# Sheet3.net
KiCad netlist of a schematic drawn in Altium Designer
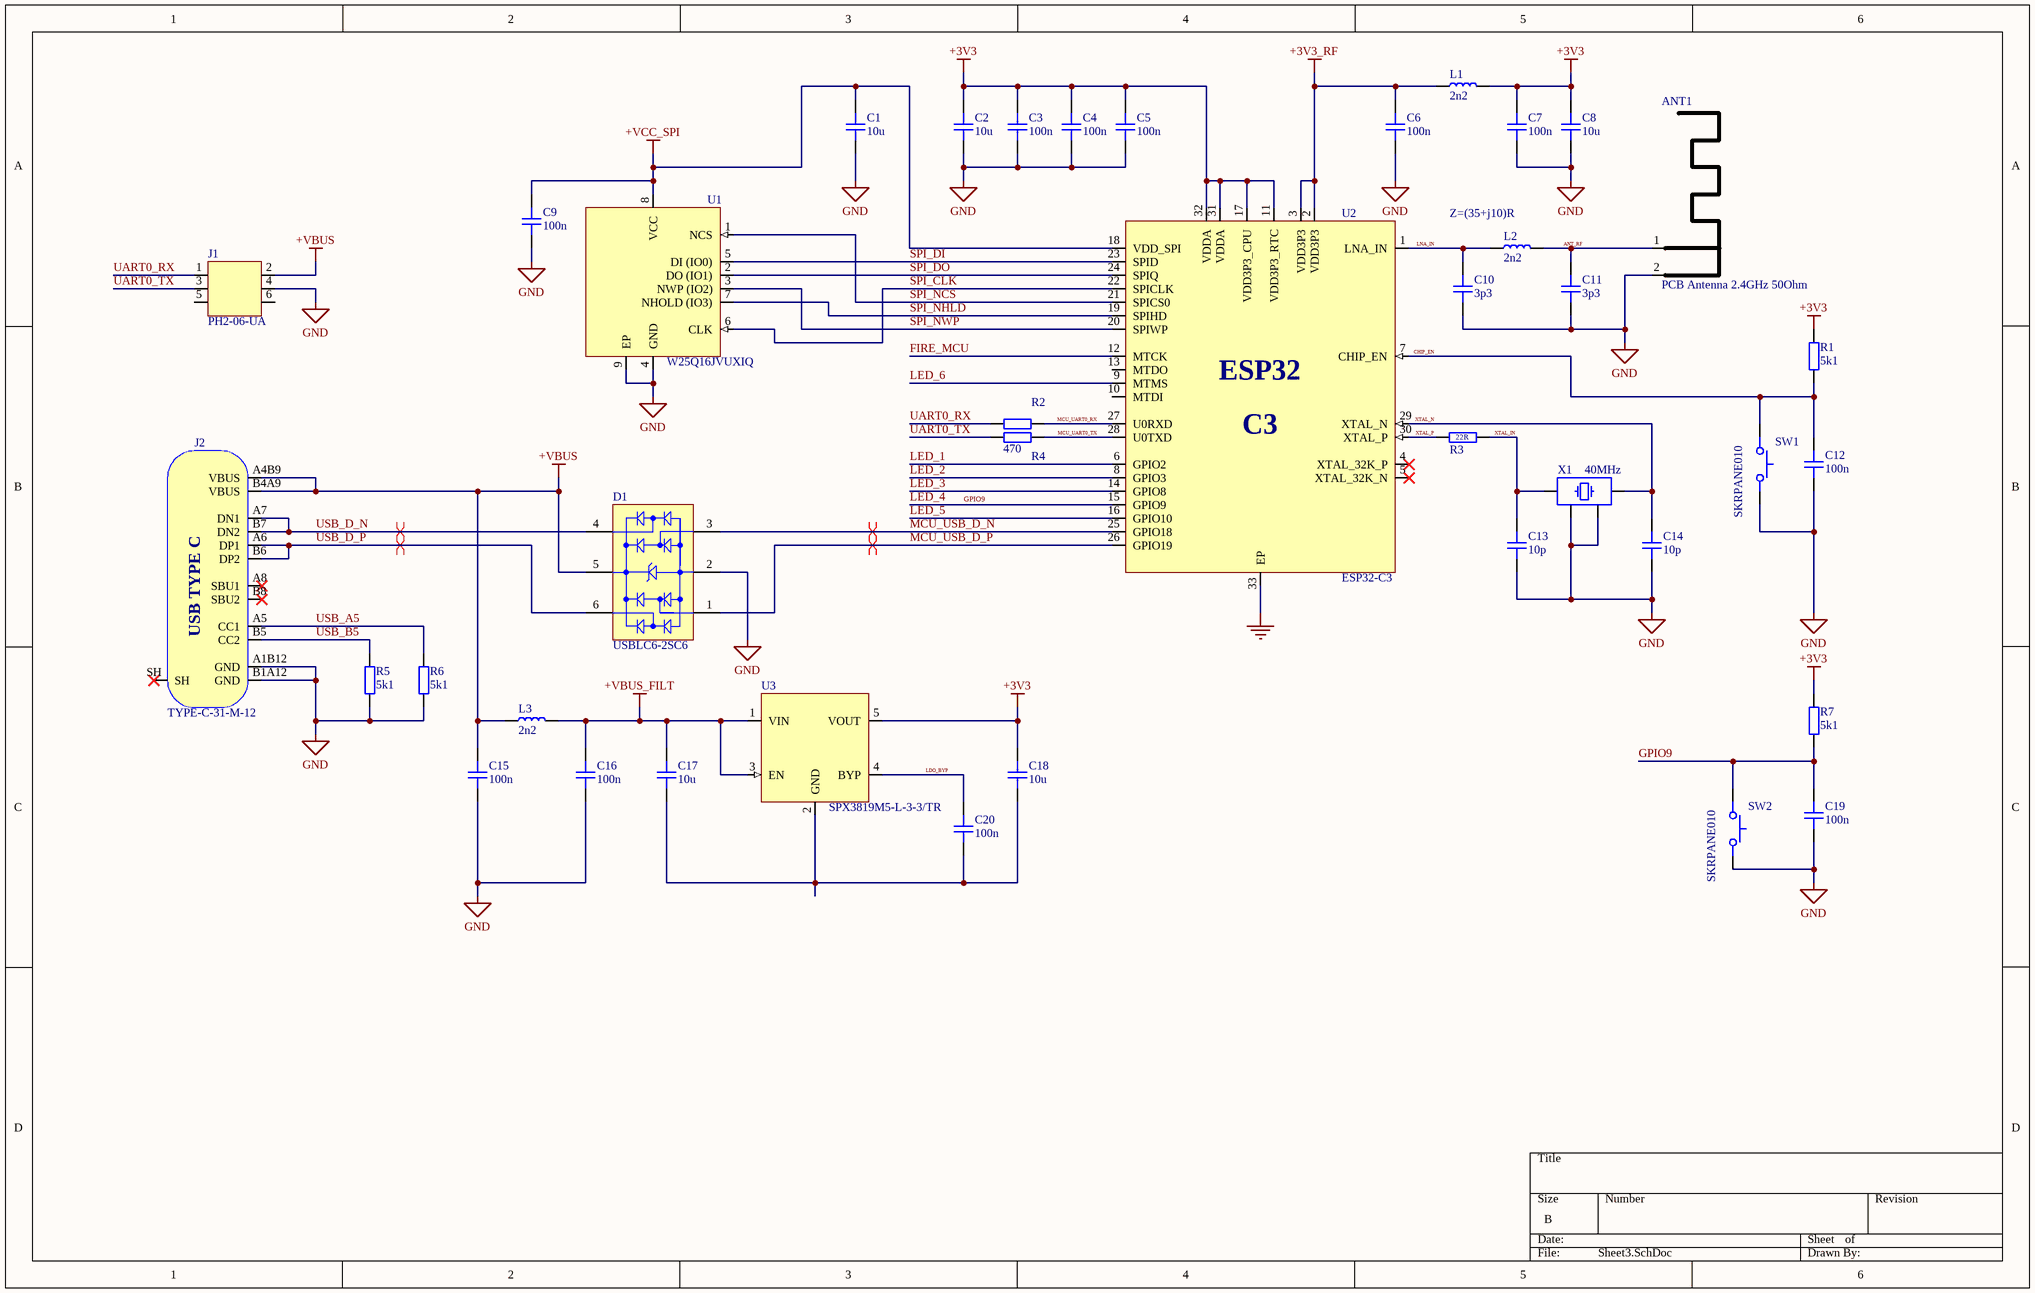
[diagram p0: Sheet3.SchDoc]

(export (version "E")
  (design (tool "Eeschema 10.0.6"))
  (components
    (comp (ref "ANT1")
      (value "PCB Antenna 2.4GHz 50Ohm")
      (footprint "ANT_IFA_USB_2_4GHZ_50R")
      (description "Inverted F 2.4GHz ISM PCB Antenna 50 Ohm")
      (libsource (lib "Schematic-Lib-PhilsLab") (part "ANT_IFA_USB_2_4GHZ_50R"))
    )
    (comp (ref "C1")
      (value "10u")
      (footprint "CAP_0603")
      (description "Capacitor SMD 0603 10V")
      (fields
        (field (name "MANUFACTURER") "Samsung")
        (field (name "MANUFACTURER PART NUMBER") "CL10A106KP8NNNC")
      )
      (libsource (lib "Schematic-Lib-PhilsLab") (part "CAP_0603_10V"))
    )
    (comp (ref "C2")
      (value "10u")
      (footprint "CAP_0603")
      (description "Capacitor SMD 0603 10V")
      (fields
        (field (name "MANUFACTURER") "Samsung")
        (field (name "MANUFACTURER PART NUMBER") "CL10A106KP8NNNC")
      )
      (libsource (lib "Schematic-Lib-PhilsLab") (part "CAP_0603_10V"))
    )
    (comp (ref "C3")
      (value "100n")
      (footprint "CAP_0805")
      (description "Capacitor SMD 0805 50V")
      (libsource (lib "Schematic-Lib-PhilsLab") (part "CAP_0805_50V"))
    )
    (comp (ref "C4")
      (value "100n")
      (footprint "CAP_0805")
      (description "Capacitor SMD 0805 50V")
      (libsource (lib "Schematic-Lib-PhilsLab") (part "CAP_0805_50V"))
    )
    (comp (ref "C5")
      (value "100n")
      (footprint "CAP_0805")
      (description "Capacitor SMD 0805 50V")
      (libsource (lib "Schematic-Lib-PhilsLab") (part "CAP_0805_50V"))
    )
    (comp (ref "C6")
      (value "100n")
      (footprint "CAP_0805")
      (description "Capacitor SMD 0805 50V")
      (libsource (lib "Schematic-Lib-PhilsLab") (part "CAP_0805_50V"))
    )
    (comp (ref "C7")
      (value "100n")
      (footprint "CAP_0805")
      (description "Capacitor SMD 0805 50V")
      (libsource (lib "Schematic-Lib-PhilsLab") (part "CAP_0805_50V"))
    )
    (comp (ref "C8")
      (value "10u")
      (footprint "CAP_0603")
      (description "Capacitor SMD 0603 10V")
      (fields
        (field (name "MANUFACTURER") "Samsung")
        (field (name "MANUFACTURER PART NUMBER") "CL10A106KP8NNNC")
      )
      (libsource (lib "Schematic-Lib-PhilsLab") (part "CAP_0603_10V"))
    )
    (comp (ref "C9")
      (value "100n")
      (footprint "CAP_0805")
      (description "Capacitor SMD 0805 50V")
      (libsource (lib "Schematic-Lib-PhilsLab") (part "CAP_0805_50V"))
    )
    (comp (ref "C10")
      (value "3p3")
      (footprint "CAP_0402")
      (description "Capacitor SMD 0402 50V")
      (fields (field (name "MANUFACTURER") "FH") (field (name "MANUFACTURER PART NUMBER") "0402CG3R3C500NT"))
      (libsource (lib "Schematic-Lib-PhilsLab") (part "CAP_0402_50V"))
    )
    (comp (ref "C11")
      (value "3p3")
      (footprint "CAP_0402")
      (description "Capacitor SMD 0402 50V")
      (fields (field (name "MANUFACTURER") "FH") (field (name "MANUFACTURER PART NUMBER") "0402CG3R3C500NT"))
      (libsource (lib "Schematic-Lib-PhilsLab") (part "CAP_0402_50V"))
    )
    (comp (ref "C12")
      (value "100n")
      (footprint "CAP_0805")
      (description "Capacitor SMD 0805 50V")
      (libsource (lib "Schematic-Lib-PhilsLab") (part "CAP_0805_50V"))
    )
    (comp (ref "C13")
      (value "10p")
      (footprint "CAP_0402")
      (description "Capacitor SMD 0402 50V")
      (fields
        (field (name "MANUFACTURER") "Samsung")
        (field (name "MANUFACTURER PART NUMBER") "CL05C100JB5NNNC")
      )
      (libsource (lib "Schematic-Lib-PhilsLab") (part "CAP_0402_50V"))
    )
    (comp (ref "C14")
      (value "10p")
      (footprint "CAP_0402")
      (description "Capacitor SMD 0402 50V")
      (fields
        (field (name "MANUFACTURER") "Samsung")
        (field (name "MANUFACTURER PART NUMBER") "CL05C100JB5NNNC")
      )
      (libsource (lib "Schematic-Lib-PhilsLab") (part "CAP_0402_50V"))
    )
    (comp (ref "C15")
      (value "100n")
      (footprint "CAP_0805")
      (description "Capacitor SMD 0805 50V")
      (libsource (lib "Schematic-Lib-PhilsLab") (part "CAP_0805_50V"))
    )
    (comp (ref "C16")
      (value "100n")
      (footprint "CAP_0805")
      (description "Capacitor SMD 0805 50V")
      (libsource (lib "Schematic-Lib-PhilsLab") (part "CAP_0805_50V"))
    )
    (comp (ref "C17")
      (value "10u")
      (footprint "CAP_0603")
      (description "Capacitor SMD 0603 10V")
      (fields
        (field (name "MANUFACTURER") "Samsung")
        (field (name "MANUFACTURER PART NUMBER") "CL10A106KP8NNNC")
      )
      (libsource (lib "Schematic-Lib-PhilsLab") (part "CAP_0603_10V"))
    )
    (comp (ref "C18")
      (value "10u")
      (footprint "CAP_0603")
      (description "Capacitor SMD 0603 10V")
      (fields
        (field (name "MANUFACTURER") "Samsung")
        (field (name "MANUFACTURER PART NUMBER") "CL10A106KP8NNNC")
      )
      (libsource (lib "Schematic-Lib-PhilsLab") (part "CAP_0603_10V"))
    )
    (comp (ref "C19")
      (value "100n")
      (footprint "CAP_0805")
      (description "Capacitor SMD 0805 50V")
      (libsource (lib "Schematic-Lib-PhilsLab") (part "CAP_0805_50V"))
    )
    (comp (ref "C20")
      (value "100n")
      (footprint "CAP_0805")
      (description "Capacitor SMD 0805 50V")
      (libsource (lib "Schematic-Lib-PhilsLab") (part "CAP_0805_50V"))
    )
    (comp (ref "D1")
      (value "USBLC6-2SC6")
      (footprint "STM-SOT23-6L_V")
      (description "Very low capacitance ESD protection, 3.5 pF, -40 to 125 degC, 6-Pin SOT23, RoHS, Tape and Reel")
      (fields (field (name "MANUFACTURER") "STMicroelectronics"))
      (libsource (lib "Altium Content Vault") (part "STM-USB_DVI_HDMIULC6-4SC6X-SOT23-6L"))
    )
    (comp (ref "J1")
      (value "PH2-06-UA")
      (footprint "PH2-06-UA")
      (libsource (lib "SchLibrary") (part "PH2-06-UA"))
    )
    (comp (ref "J2")
      (value "TYPE-C-31-M-12")
      (footprint "TYPE-C-31-M-12")
      (description "USB Type C Connector Horizontal SMT")
      (fields (field (name "MANUFACTURER") "Koren Hroparts"))
      (libsource (lib "Schematic-Lib-PhilsLab") (part "TYPE-C-31-M-12"))
    )
    (comp (ref "L1")
      (value "2n2")
      (footprint "IND_0402")
      (description "Inductor SMD 0402")
      (fields
        (field (name "MANUFACTURER") "Murata")
        (field (name "MANUFACTURER PART NUMBER") "LQW15AN2N2G80D")
      )
      (libsource (lib "Schematic-Lib-PhilsLab") (part "IND_0402"))
    )
    (comp (ref "L2")
      (value "2n2")
      (footprint "IND_0402")
      (description "Inductor SMD 0402")
      (fields
        (field (name "MANUFACTURER") "Murata")
        (field (name "MANUFACTURER PART NUMBER") "LQW15AN2N2G80D")
      )
      (libsource (lib "Schematic-Lib-PhilsLab") (part "IND_0402"))
    )
    (comp (ref "L3")
      (value "2n2")
      (footprint "IND_0402")
      (description "Inductor SMD 0402")
      (fields
        (field (name "MANUFACTURER") "Murata")
        (field (name "MANUFACTURER PART NUMBER") "LQW15AN2N2G80D")
      )
      (libsource (lib "Schematic-Lib-PhilsLab") (part "IND_0402"))
    )
    (comp (ref "R1")
      (value "5k1")
      (footprint "RES_0805")
      (description "Resistor SMD 0805")
      (libsource (lib "Schematic-Lib-PhilsLab") (part "RES_0805"))
    )
    (comp (ref "R2")
      (value "470")
      (footprint "RES_0805")
      (description "Resistor SMD 0805")
      (libsource (lib "Schematic-Lib-PhilsLab") (part "RES_0805"))
    )
    (comp (ref "R3")
      (value "22R")
      (footprint "RES_0402")
      (description "Resistor SMD 0402")
      (fields
        (field (name "MANUFACTURER") "UNI-ROYAL")
        (field (name "MANUFACTURER PART NUMBER") "0402WGF220JTCE")
      )
      (libsource (lib "Schematic-Lib-PhilsLab") (part "RES_0402"))
    )
    (comp (ref "R4")
      (value "470")
      (footprint "RES_0805")
      (description "Resistor SMD 0805")
      (libsource (lib "Schematic-Lib-PhilsLab") (part "RES_0805"))
    )
    (comp (ref "R5")
      (value "5k1")
      (footprint "RES_0805")
      (description "Resistor SMD 0805")
      (libsource (lib "Schematic-Lib-PhilsLab") (part "RES_0805"))
    )
    (comp (ref "R6")
      (value "5k1")
      (footprint "RES_0805")
      (description "Resistor SMD 0805")
      (libsource (lib "Schematic-Lib-PhilsLab") (part "RES_0805"))
    )
    (comp (ref "R7")
      (value "5k1")
      (footprint "RES_0805")
      (description "Resistor SMD 0805")
      (libsource (lib "Schematic-Lib-PhilsLab") (part "RES_0805"))
    )
    (comp (ref "SW1")
      (value "SKRPANE010")
      (footprint "SKRPANE010")
      (description "Tactile Switch SMD SPST")
      (fields (field (name "MANUFACTURER") "Alps Alpine"))
      (libsource (lib "Schematic-Lib-PhilsLab") (part "SKRPANE010"))
    )
    (comp (ref "SW2")
      (value "SKRPANE010")
      (footprint "SKRPANE010")
      (description "Tactile Switch SMD SPST")
      (fields (field (name "MANUFACTURER") "Alps Alpine"))
      (libsource (lib "Schematic-Lib-PhilsLab") (part "SKRPANE010"))
    )
    (comp (ref "U1")
      (value "W25Q16JVUXIQ")
      (footprint "USON-8-2X3MM")
      (description "16M-BIT SERIAL FLASH MEMORY WITH\r\nDUAL/QUAD SPI USON-8")
      (fields (field (name "MANUFACTURER") "Winbond"))
      (libsource (lib "Schematic-Lib-PhilsLab") (part "W25Q16JVUXIQ"))
    )
    (comp (ref "U2")
      (value "ESP32-C3")
      (footprint "QFN32-5x5")
      (fields (field (name "MANUFACTURER") "Espressif"))
      (libsource (lib "Schematic-Lib-PhilsLab") (part "ESP32-C3"))
    )
    (comp (ref "U3")
      (value "SPX3819M5-L-3-3/TR")
      (footprint "SOT-23-5")
      (description "500mA +3.3V Low-Noise LDO Voltage Regulator")
      (fields (field (name "MANUFACTURER") "MaxLinear"))
      (libsource (lib "Schematic-Lib-PhilsLab") (part "SPX3819M5-L-3-3/TR"))
    )
    (comp (ref "X1")
      (value "40MHz")
      (footprint "XTAL_2520")
      (description "Crystal SMD 2520")
      (fields (field (name "MANUFACTURER") "Seiko Epson"))
      (libsource (lib "Schematic-Lib-PhilsLab") (part "XTAL_2520"))
    )
  )
  (nets
    (net (code "1") (name "+3V3") (class "Default")
      (node (ref "C18") (pin "2") (pinfunction "2_2") (pintype "passive"))
      (node (ref "C2") (pin "2") (pinfunction "2_2") (pintype "passive"))
      (node (ref "C3") (pin "2") (pinfunction "2_2") (pintype "passive"))
      (node (ref "C4") (pin "2") (pinfunction "2_2") (pintype "passive"))
      (node (ref "C5") (pin "2") (pinfunction "2_2") (pintype "passive"))
      (node (ref "C7") (pin "2") (pinfunction "2_2") (pintype "passive"))
      (node (ref "C8") (pin "2") (pinfunction "2_2") (pintype "passive"))
      (node (ref "L1") (pin "1") (pinfunction "1_1") (pintype "passive"))
      (node (ref "R1") (pin "2") (pinfunction "2_2") (pintype "passive"))
      (node (ref "R7") (pin "2") (pinfunction "2_2") (pintype "passive"))
      (node (ref "U2") (pin "11") (pinfunction "VDD3P3_RTC_11") (pintype "power_in"))
      (node (ref "U2") (pin "17") (pinfunction "VDD3P3_CPU_17") (pintype "power_in"))
      (node (ref "U2") (pin "31") (pinfunction "VDDA_31") (pintype "power_in"))
      (node (ref "U2") (pin "32") (pinfunction "VDDA_32") (pintype "power_in"))
      (node (ref "U3") (pin "5") (pinfunction "VOUT_5") (pintype "power_in"))
    )
    (net (code "2") (name "+3V3_RF") (class "Default")
      (node (ref "C6") (pin "2") (pinfunction "2_2") (pintype "passive"))
      (node (ref "L1") (pin "2") (pinfunction "2_2") (pintype "passive"))
      (node (ref "U2") (pin "2") (pinfunction "VDD3P3_2") (pintype "power_in"))
      (node (ref "U2") (pin "3") (pinfunction "VDD3P3_3") (pintype "power_in"))
    )
    (net (code "3") (name "+VBUS") (class "Default")
      (node (ref "C15") (pin "2") (pinfunction "2_2") (pintype "passive"))
      (node (ref "D1") (pin "5") (pinfunction "VBUS_5") (pintype "passive"))
      (node (ref "J1") (pin "2") (pinfunction "2_2") (pintype "passive"))
      (node (ref "J2") (pin "A4B9") (pinfunction "VBUS_A4B9") (pintype "power_in"))
      (node (ref "J2") (pin "B4A9") (pinfunction "VBUS_B4A9") (pintype "power_in"))
      (node (ref "L3") (pin "2") (pinfunction "2_2") (pintype "passive"))
    )
    (net (code "4") (name "+VBUS_FILT") (class "Default")
      (node (ref "C16") (pin "2") (pinfunction "2_2") (pintype "passive"))
      (node (ref "C17") (pin "2") (pinfunction "2_2") (pintype "passive"))
      (node (ref "L3") (pin "1") (pinfunction "1_1") (pintype "passive"))
      (node (ref "U3") (pin "1") (pinfunction "VIN_1") (pintype "power_in"))
      (node (ref "U3") (pin "3") (pinfunction "EN_3") (pintype "input"))
    )
    (net (code "5") (name "+VCC_SPI") (class "Default")
      (node (ref "C1") (pin "2") (pinfunction "2_2") (pintype "passive"))
      (node (ref "C9") (pin "2") (pinfunction "2_2") (pintype "passive"))
      (node (ref "U1") (pin "8") (pinfunction "VCC_8") (pintype "power_in"))
      (node (ref "U2") (pin "18") (pinfunction "VDD_SPI_18") (pintype "power_in"))
    )
    (net (code "6") (name "/ANT_RF") (class "Default")
      (node (ref "ANT1") (pin "1") (pinfunction "RF_1") (pintype "passive"))
      (node (ref "C11") (pin "2") (pinfunction "2_2") (pintype "passive"))
      (node (ref "L2") (pin "1") (pinfunction "1_1") (pintype "passive"))
    )
    (net (code "7") (name "/CHIP_EN") (class "Default")
      (node (ref "C12") (pin "2") (pinfunction "2_2") (pintype "passive"))
      (node (ref "R1") (pin "1") (pinfunction "1_1") (pintype "passive"))
      (node (ref "SW1") (pin "34") (pintype "passive"))
      (node (ref "U2") (pin "7") (pinfunction "CHIP_EN_7") (pintype "input"))
    )
    (net (code "8") (name "/FIRE_MCU") (class "Default")
      (node (ref "U2") (pin "12") (pinfunction "MTCK_12") (pintype "bidirectional"))
    )
    (net (code "9") (name "/GPIO9") (class "Default")
      (node (ref "C19") (pin "2") (pinfunction "2_2") (pintype "passive"))
      (node (ref "R7") (pin "1") (pinfunction "1_1") (pintype "passive"))
      (node (ref "SW2") (pin "34") (pintype "passive"))
      (node (ref "U2") (pin "15") (pinfunction "GPIO9_15") (pintype "bidirectional"))
    )
    (net (code "10") (name "/LDO_BYP") (class "Default")
      (node (ref "C20") (pin "2") (pinfunction "2_2") (pintype "passive"))
      (node (ref "U3") (pin "4") (pinfunction "BYP_4") (pintype "passive"))
    )
    (net (code "11") (name "/LED_1") (class "Default")
      (node (ref "U2") (pin "6") (pinfunction "GPIO2_6") (pintype "bidirectional"))
    )
    (net (code "12") (name "/LED_2") (class "Default")
      (node (ref "U2") (pin "8") (pinfunction "GPIO3_8") (pintype "bidirectional"))
    )
    (net (code "13") (name "/LED_3") (class "Default")
      (node (ref "U2") (pin "14") (pinfunction "GPIO8_14") (pintype "bidirectional"))
    )
    (net (code "14") (name "/LED_5") (class "Default")
      (node (ref "U2") (pin "16") (pinfunction "GPIO10_16") (pintype "bidirectional"))
    )
    (net (code "15") (name "/LED_6") (class "Default")
      (node (ref "U2") (pin "9") (pinfunction "MTMS_9") (pintype "bidirectional"))
    )
    (net (code "16") (name "/LNA_IN") (class "Default")
      (node (ref "C10") (pin "2") (pinfunction "2_2") (pintype "passive"))
      (node (ref "L2") (pin "2") (pinfunction "2_2") (pintype "passive"))
      (node (ref "U2") (pin "1") (pinfunction "LNA_IN_1") (pintype "bidirectional"))
    )
    (net (code "17") (name "/MCU_UART0_RX") (class "Default")
      (node (ref "R2") (pin "1") (pinfunction "1_1") (pintype "passive"))
      (node (ref "U2") (pin "27") (pinfunction "U0RXD_27") (pintype "bidirectional"))
    )
    (net (code "18") (name "/MCU_UART0_TX") (class "Default")
      (node (ref "R4") (pin "1") (pinfunction "1_1") (pintype "passive"))
      (node (ref "U2") (pin "28") (pinfunction "U0TXD_28") (pintype "bidirectional"))
    )
    (net (code "19") (name "/MCU_USB_D_N") (class "Default")
      (node (ref "D1") (pin "3") (pinfunction "I/O_2_3") (pintype "passive"))
      (node (ref "U2") (pin "25") (pinfunction "GPIO18_25") (pintype "bidirectional"))
    )
    (net (code "20") (name "/MCU_USB_D_P") (class "Default")
      (node (ref "D1") (pin "1") (pinfunction "I/O_1_1") (pintype "passive"))
      (node (ref "U2") (pin "26") (pinfunction "GPIO19_26") (pintype "bidirectional"))
    )
    (net (code "21") (name "/SPI_CLK") (class "Default")
      (node (ref "U1") (pin "6") (pinfunction "CLK_6") (pintype "input"))
      (node (ref "U2") (pin "22") (pinfunction "SPICLK_22") (pintype "bidirectional"))
    )
    (net (code "22") (name "/SPI_DI") (class "Default")
      (node (ref "U1") (pin "5") (pinfunction "DI_(IO0)_5") (pintype "bidirectional"))
      (node (ref "U2") (pin "23") (pinfunction "SPID_23") (pintype "bidirectional"))
    )
    (net (code "23") (name "/SPI_DO") (class "Default")
      (node (ref "U1") (pin "2") (pinfunction "DO_(IO1)_2") (pintype "bidirectional"))
      (node (ref "U2") (pin "24") (pinfunction "SPIQ_24") (pintype "bidirectional"))
    )
    (net (code "24") (name "/SPI_NCS") (class "Default")
      (node (ref "U1") (pin "1") (pinfunction "NCS_1") (pintype "input"))
      (node (ref "U2") (pin "21") (pinfunction "SPICS0_21") (pintype "bidirectional"))
    )
    (net (code "25") (name "/SPI_NHLD") (class "Default")
      (node (ref "U1") (pin "7") (pinfunction "NHOLD_(IO3)_7") (pintype "bidirectional"))
      (node (ref "U2") (pin "19") (pinfunction "SPIHD_19") (pintype "bidirectional"))
    )
    (net (code "26") (name "/SPI_NWP") (class "Default")
      (node (ref "U1") (pin "3") (pinfunction "NWP_(IO2)_3") (pintype "bidirectional"))
      (node (ref "U2") (pin "20") (pinfunction "SPIWP_20") (pintype "bidirectional"))
    )
    (net (code "27") (name "/UART0_RX") (class "Default")
      (node (ref "J1") (pin "1") (pinfunction "1_1") (pintype "passive"))
      (node (ref "R2") (pin "2") (pinfunction "2_2") (pintype "passive"))
    )
    (net (code "28") (name "/UART0_TX") (class "Default")
      (node (ref "J1") (pin "3") (pinfunction "3_3") (pintype "passive"))
      (node (ref "R4") (pin "2") (pinfunction "2_2") (pintype "passive"))
    )
    (net (code "29") (name "/USB_A5") (class "Default")
      (node (ref "J2") (pin "A5") (pinfunction "CC1_A5") (pintype "passive"))
      (node (ref "R6") (pin "2") (pinfunction "2_2") (pintype "passive"))
    )
    (net (code "30") (name "/USB_B5") (class "Default")
      (node (ref "J2") (pin "B5") (pinfunction "CC2_B5") (pintype "tri_state"))
      (node (ref "R5") (pin "2") (pinfunction "2_2") (pintype "passive"))
    )
    (net (code "31") (name "/USB_D_N") (class "Default")
      (node (ref "D1") (pin "4") (pinfunction "I/O_3_4") (pintype "passive"))
      (node (ref "J2") (pin "A7") (pinfunction "DN1_A7") (pintype "bidirectional"))
      (node (ref "J2") (pin "B7") (pinfunction "DN2_B7") (pintype "bidirectional"))
    )
    (net (code "32") (name "/USB_D_P") (class "Default")
      (node (ref "D1") (pin "6") (pinfunction "I/O_4_6") (pintype "passive"))
      (node (ref "J2") (pin "A6") (pinfunction "DP1_A6") (pintype "bidirectional"))
      (node (ref "J2") (pin "B6") (pinfunction "DP2_B6") (pintype "bidirectional"))
    )
    (net (code "33") (name "/XTAL_IN") (class "Default")
      (node (ref "C13") (pin "2") (pinfunction "2_2") (pintype "passive"))
      (node (ref "R3") (pin "2") (pinfunction "2_2") (pintype "passive"))
      (node (ref "X1") (pin "3") (pinfunction "3_3") (pintype "passive"))
    )
    (net (code "34") (name "/XTAL_N") (class "Default")
      (node (ref "C14") (pin "2") (pinfunction "2_2") (pintype "passive"))
      (node (ref "U2") (pin "29") (pinfunction "XTAL_N_29") (pintype "input"))
      (node (ref "X1") (pin "1") (pinfunction "1_1") (pintype "passive"))
    )
    (net (code "35") (name "/XTAL_P") (class "Default")
      (node (ref "R3") (pin "1") (pinfunction "1_1") (pintype "passive"))
      (node (ref "U2") (pin "30") (pinfunction "XTAL_P_30") (pintype "input"))
    )
    (net (code "36") (name "GND") (class "Default")
      (node (ref "ANT1") (pin "2") (pinfunction "GND_2") (pintype "passive"))
      (node (ref "C1") (pin "1") (pinfunction "1_1") (pintype "passive"))
      (node (ref "C10") (pin "1") (pinfunction "1_1") (pintype "passive"))
      (node (ref "C11") (pin "1") (pinfunction "1_1") (pintype "passive"))
      (node (ref "C12") (pin "1") (pinfunction "1_1") (pintype "passive"))
      (node (ref "C13") (pin "1") (pinfunction "1_1") (pintype "passive"))
      (node (ref "C14") (pin "1") (pinfunction "1_1") (pintype "passive"))
      (node (ref "C15") (pin "1") (pinfunction "1_1") (pintype "passive"))
      (node (ref "C16") (pin "1") (pinfunction "1_1") (pintype "passive"))
      (node (ref "C19") (pin "1") (pinfunction "1_1") (pintype "passive"))
      (node (ref "C2") (pin "1") (pinfunction "1_1") (pintype "passive"))
      (node (ref "C3") (pin "1") (pinfunction "1_1") (pintype "passive"))
      (node (ref "C4") (pin "1") (pinfunction "1_1") (pintype "passive"))
      (node (ref "C5") (pin "1") (pinfunction "1_1") (pintype "passive"))
      (node (ref "C6") (pin "1") (pinfunction "1_1") (pintype "passive"))
      (node (ref "C7") (pin "1") (pinfunction "1_1") (pintype "passive"))
      (node (ref "C8") (pin "1") (pinfunction "1_1") (pintype "passive"))
      (node (ref "C9") (pin "1") (pinfunction "1_1") (pintype "passive"))
      (node (ref "D1") (pin "2") (pinfunction "GND_2") (pintype "passive"))
      (node (ref "J1") (pin "4") (pinfunction "4_4") (pintype "passive"))
      (node (ref "J2") (pin "A1B12") (pinfunction "GND_A1B12") (pintype "power_in"))
      (node (ref "J2") (pin "B1A12") (pinfunction "GND_B1A12") (pintype "power_in"))
      (node (ref "R5") (pin "1") (pinfunction "1_1") (pintype "passive"))
      (node (ref "R6") (pin "1") (pinfunction "1_1") (pintype "passive"))
      (node (ref "SW1") (pin "12") (pintype "passive"))
      (node (ref "SW2") (pin "12") (pintype "passive"))
      (node (ref "U1") (pin "4") (pinfunction "GND_4") (pintype "power_in"))
      (node (ref "U1") (pin "9") (pinfunction "EP_9") (pintype "power_in"))
      (node (ref "U2") (pin "33") (pinfunction "EP_33") (pintype "power_in"))
      (node (ref "X1") (pin "2") (pinfunction "2_2") (pintype "passive"))
      (node (ref "X1") (pin "4") (pinfunction "4_4") (pintype "passive"))
    )
    (net (code "37") (name "Net-(U3-GND)") (class "Default")
      (node (ref "C17") (pin "1") (pinfunction "1_1") (pintype "passive"))
      (node (ref "C18") (pin "1") (pinfunction "1_1") (pintype "passive"))
      (node (ref "C20") (pin "1") (pinfunction "1_1") (pintype "passive"))
      (node (ref "U3") (pin "2") (pinfunction "GND_2") (pintype "power_in"))
    )
    (net (code "38") (name "unconnected-(J1-Pad5)") (class "Default")
      (node (ref "J1") (pin "5") (pinfunction "5_5") (pintype "passive"))
    )
    (net (code "39") (name "unconnected-(J1-Pad6)") (class "Default")
      (node (ref "J1") (pin "6") (pinfunction "6_6") (pintype "passive"))
    )
    (net (code "40") (name "unconnected-(J2-PadSH)") (class "Default")
      (node (ref "J2") (pin "SH") (pinfunction "SH_SH") (pintype "power_in+no_connect"))
    )
    (net (code "41") (name "unconnected-(J2-SBU1-PadA8)") (class "Default")
      (node (ref "J2") (pin "A8") (pinfunction "SBU1_A8") (pintype "bidirectional+no_connect"))
    )
    (net (code "42") (name "unconnected-(J2-SBU2-PadB8)") (class "Default")
      (node (ref "J2") (pin "B8") (pinfunction "SBU2_B8") (pintype "bidirectional+no_connect"))
    )
    (net (code "43") (name "unconnected-(U2-MTDI-Pad10)") (class "Default")
      (node (ref "U2") (pin "10") (pinfunction "MTDI_10") (pintype "bidirectional"))
    )
    (net (code "44") (name "unconnected-(U2-MTDO-Pad13)") (class "Default")
      (node (ref "U2") (pin "13") (pinfunction "MTDO_13") (pintype "bidirectional"))
    )
    (net (code "45") (name "unconnected-(U2-XTAL_32K_N-Pad5)") (class "Default")
      (node (ref "U2") (pin "5") (pinfunction "XTAL_32K_N_5") (pintype "bidirectional+no_connect"))
    )
    (net (code "46") (name "unconnected-(U2-XTAL_32K_P-Pad4)") (class "Default")
      (node (ref "U2") (pin "4") (pinfunction "XTAL_32K_P_4") (pintype "bidirectional+no_connect"))
    )
  )
)
